# rev02_16.net
KiCad netlist of a schematic drawn in Altium Designer
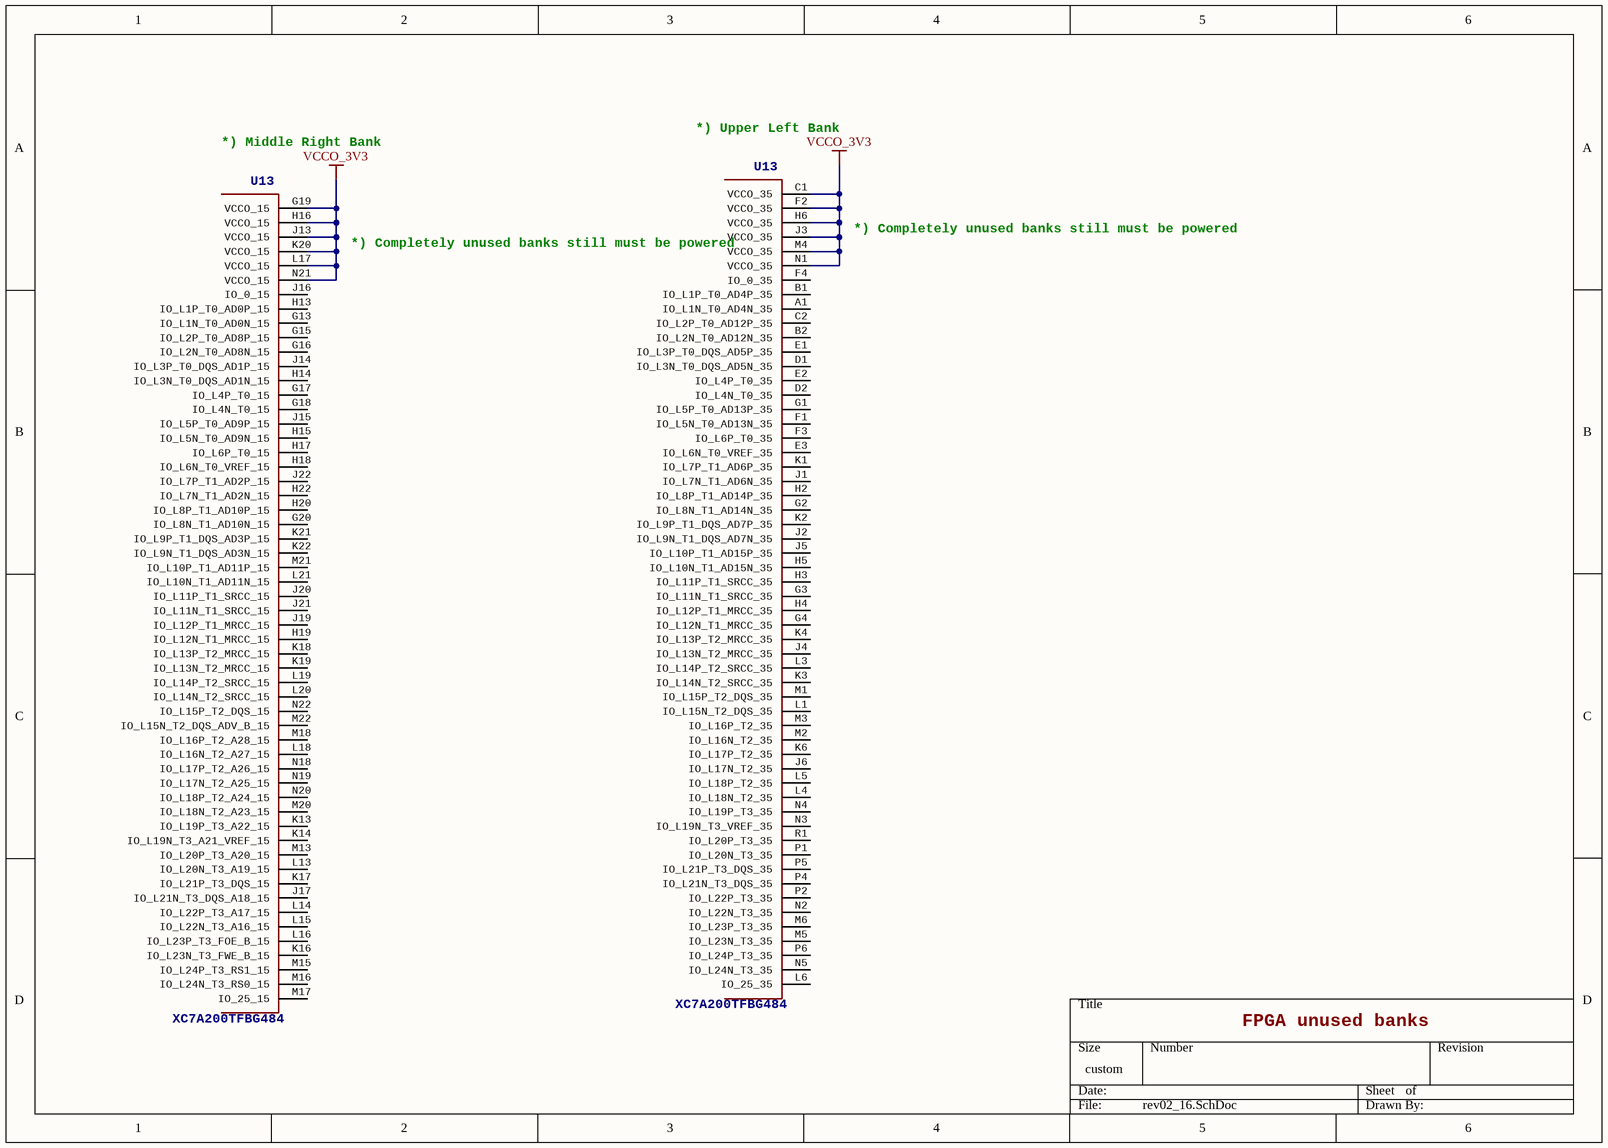
[diagram p0: rev02_16.SchDoc]

(export (version "E")
  (design (tool "Eeschema 10.0.6"))
  (components
    (comp (ref "U13")
      (value "XC7A200TFBG484")
      (footprint "BGA484C100P22X22_2300X2300X254")
      (description "Xilinx FPGA: XC7A200TFBG484")
      (fields
        (field (name "MFR") "Xilinx")
        (field (name "MPN") "XC7A200T-1FBG484C")
        (field (name ">NAME") "U13")
        (field (name ">VALUE") "XC7A200TFBG484")
      )
      (libsource (lib "Xilinx_XC7A200TFBG484") (part "XC7A200TFBG484"))
    )
  )
  (nets
    (net (code "1") (name "VCCO_3V3") (class "Default")
      (node (ref "U13") (pin "C1") (pinfunction "VCCO_35_C1") (pintype "passive"))
      (node (ref "U13") (pin "F2") (pinfunction "VCCO_35_F2") (pintype "passive"))
      (node (ref "U13") (pin "G19") (pinfunction "VCCO_15_G19") (pintype "passive"))
      (node (ref "U13") (pin "H16") (pinfunction "VCCO_15_H16") (pintype "passive"))
      (node (ref "U13") (pin "H6") (pinfunction "VCCO_35_H6") (pintype "passive"))
      (node (ref "U13") (pin "J13") (pinfunction "VCCO_15_J13") (pintype "passive"))
      (node (ref "U13") (pin "J3") (pinfunction "VCCO_35_J3") (pintype "passive"))
      (node (ref "U13") (pin "K20") (pinfunction "VCCO_15_K20") (pintype "passive"))
      (node (ref "U13") (pin "L17") (pinfunction "VCCO_15_L17") (pintype "passive"))
      (node (ref "U13") (pin "M4") (pinfunction "VCCO_35_M4") (pintype "passive"))
      (node (ref "U13") (pin "N1") (pinfunction "VCCO_35_N1") (pintype "passive"))
      (node (ref "U13") (pin "N21") (pinfunction "VCCO_15_N21") (pintype "passive"))
    )
    (net (code "2") (name "unconnected-(U13D-IO_0_15-PadJ16)") (class "Default")
      (node (ref "U13") (pin "J16") (pinfunction "IO_0_15_J16") (pintype "passive"))
    )
    (net (code "3") (name "unconnected-(U13D-IO_25_15-PadM17)") (class "Default")
      (node (ref "U13") (pin "M17") (pinfunction "IO_25_15_M17") (pintype "passive"))
    )
    (net (code "4") (name "unconnected-(U13D-IO_L1N_T0_AD0N_15-PadG13)") (class "Default")
      (node (ref "U13") (pin "G13") (pinfunction "IO_L1N_T0_AD0N_15_G13") (pintype "passive"))
    )
    (net (code "5") (name "unconnected-(U13D-IO_L1P_T0_AD0P_15-PadH13)") (class "Default")
      (node (ref "U13") (pin "H13") (pinfunction "IO_L1P_T0_AD0P_15_H13") (pintype "passive"))
    )
    (net (code "6") (name "unconnected-(U13D-IO_L2N_T0_AD8N_15-PadG16)") (class "Default")
      (node (ref "U13") (pin "G16") (pinfunction "IO_L2N_T0_AD8N_15_G16") (pintype "passive"))
    )
    (net (code "7") (name "unconnected-(U13D-IO_L2P_T0_AD8P_15-PadG15)") (class "Default")
      (node (ref "U13") (pin "G15") (pinfunction "IO_L2P_T0_AD8P_15_G15") (pintype "passive"))
    )
    (net (code "8") (name "unconnected-(U13D-IO_L3N_T0_DQS_AD1N_15-PadH14)") (class "Default")
      (node (ref "U13") (pin "H14") (pinfunction "IO_L3N_T0_DQS_AD1N_15_H14") (pintype "passive"))
    )
    (net (code "9") (name "unconnected-(U13D-IO_L3P_T0_DQS_AD1P_15-PadJ14)") (class "Default")
      (node (ref "U13") (pin "J14") (pinfunction "IO_L3P_T0_DQS_AD1P_15_J14") (pintype "passive"))
    )
    (net (code "10") (name "unconnected-(U13D-IO_L4N_T0_15-PadG18)") (class "Default")
      (node (ref "U13") (pin "G18") (pinfunction "IO_L4N_T0_15_G18") (pintype "passive"))
    )
    (net (code "11") (name "unconnected-(U13D-IO_L4P_T0_15-PadG17)") (class "Default")
      (node (ref "U13") (pin "G17") (pinfunction "IO_L4P_T0_15_G17") (pintype "passive"))
    )
    (net (code "12") (name "unconnected-(U13D-IO_L5N_T0_AD9N_15-PadH15)") (class "Default")
      (node (ref "U13") (pin "H15") (pinfunction "IO_L5N_T0_AD9N_15_H15") (pintype "passive"))
    )
    (net (code "13") (name "unconnected-(U13D-IO_L5P_T0_AD9P_15-PadJ15)") (class "Default")
      (node (ref "U13") (pin "J15") (pinfunction "IO_L5P_T0_AD9P_15_J15") (pintype "passive"))
    )
    (net (code "14") (name "unconnected-(U13D-IO_L6N_T0_VREF_15-PadH18)") (class "Default")
      (node (ref "U13") (pin "H18") (pinfunction "IO_L6N_T0_VREF_15_H18") (pintype "passive"))
    )
    (net (code "15") (name "unconnected-(U13D-IO_L6P_T0_15-PadH17)") (class "Default")
      (node (ref "U13") (pin "H17") (pinfunction "IO_L6P_T0_15_H17") (pintype "passive"))
    )
    (net (code "16") (name "unconnected-(U13D-IO_L7N_T1_AD2N_15-PadH22)") (class "Default")
      (node (ref "U13") (pin "H22") (pinfunction "IO_L7N_T1_AD2N_15_H22") (pintype "passive"))
    )
    (net (code "17") (name "unconnected-(U13D-IO_L7P_T1_AD2P_15-PadJ22)") (class "Default")
      (node (ref "U13") (pin "J22") (pinfunction "IO_L7P_T1_AD2P_15_J22") (pintype "passive"))
    )
    (net (code "18") (name "unconnected-(U13D-IO_L8N_T1_AD10N_15-PadG20)") (class "Default")
      (node (ref "U13") (pin "G20") (pinfunction "IO_L8N_T1_AD10N_15_G20") (pintype "passive"))
    )
    (net (code "19") (name "unconnected-(U13D-IO_L8P_T1_AD10P_15-PadH20)") (class "Default")
      (node (ref "U13") (pin "H20") (pinfunction "IO_L8P_T1_AD10P_15_H20") (pintype "passive"))
    )
    (net (code "20") (name "unconnected-(U13D-IO_L9N_T1_DQS_AD3N_15-PadK22)") (class "Default")
      (node (ref "U13") (pin "K22") (pinfunction "IO_L9N_T1_DQS_AD3N_15_K22") (pintype "passive"))
    )
    (net (code "21") (name "unconnected-(U13D-IO_L9P_T1_DQS_AD3P_15-PadK21)") (class "Default")
      (node (ref "U13") (pin "K21") (pinfunction "IO_L9P_T1_DQS_AD3P_15_K21") (pintype "passive"))
    )
    (net (code "22") (name "unconnected-(U13D-IO_L10N_T1_AD11N_15-PadL21)") (class "Default")
      (node (ref "U13") (pin "L21") (pinfunction "IO_L10N_T1_AD11N_15_L21") (pintype "passive"))
    )
    (net (code "23") (name "unconnected-(U13D-IO_L10P_T1_AD11P_15-PadM21)") (class "Default")
      (node (ref "U13") (pin "M21") (pinfunction "IO_L10P_T1_AD11P_15_M21") (pintype "passive"))
    )
    (net (code "24") (name "unconnected-(U13D-IO_L11N_T1_SRCC_15-PadJ21)") (class "Default")
      (node (ref "U13") (pin "J21") (pinfunction "IO_L11N_T1_SRCC_15_J21") (pintype "passive"))
    )
    (net (code "25") (name "unconnected-(U13D-IO_L11P_T1_SRCC_15-PadJ20)") (class "Default")
      (node (ref "U13") (pin "J20") (pinfunction "IO_L11P_T1_SRCC_15_J20") (pintype "passive"))
    )
    (net (code "26") (name "unconnected-(U13D-IO_L12N_T1_MRCC_15-PadH19)") (class "Default")
      (node (ref "U13") (pin "H19") (pinfunction "IO_L12N_T1_MRCC_15_H19") (pintype "passive"))
    )
    (net (code "27") (name "unconnected-(U13D-IO_L12P_T1_MRCC_15-PadJ19)") (class "Default")
      (node (ref "U13") (pin "J19") (pinfunction "IO_L12P_T1_MRCC_15_J19") (pintype "passive"))
    )
    (net (code "28") (name "unconnected-(U13D-IO_L13N_T2_MRCC_15-PadK19)") (class "Default")
      (node (ref "U13") (pin "K19") (pinfunction "IO_L13N_T2_MRCC_15_K19") (pintype "passive"))
    )
    (net (code "29") (name "unconnected-(U13D-IO_L13P_T2_MRCC_15-PadK18)") (class "Default")
      (node (ref "U13") (pin "K18") (pinfunction "IO_L13P_T2_MRCC_15_K18") (pintype "passive"))
    )
    (net (code "30") (name "unconnected-(U13D-IO_L14N_T2_SRCC_15-PadL20)") (class "Default")
      (node (ref "U13") (pin "L20") (pinfunction "IO_L14N_T2_SRCC_15_L20") (pintype "passive"))
    )
    (net (code "31") (name "unconnected-(U13D-IO_L14P_T2_SRCC_15-PadL19)") (class "Default")
      (node (ref "U13") (pin "L19") (pinfunction "IO_L14P_T2_SRCC_15_L19") (pintype "passive"))
    )
    (net (code "32") (name "unconnected-(U13D-IO_L15N_T2_DQS_ADV_B_15-PadM22)") (class "Default")
      (node (ref "U13") (pin "M22") (pinfunction "IO_L15N_T2_DQS_ADV_B_15_M22") (pintype "passive"))
    )
    (net (code "33") (name "unconnected-(U13D-IO_L15P_T2_DQS_15-PadN22)") (class "Default")
      (node (ref "U13") (pin "N22") (pinfunction "IO_L15P_T2_DQS_15_N22") (pintype "passive"))
    )
    (net (code "34") (name "unconnected-(U13D-IO_L16N_T2_A27_15-PadL18)") (class "Default")
      (node (ref "U13") (pin "L18") (pinfunction "IO_L16N_T2_A27_15_L18") (pintype "passive"))
    )
    (net (code "35") (name "unconnected-(U13D-IO_L16P_T2_A28_15-PadM18)") (class "Default")
      (node (ref "U13") (pin "M18") (pinfunction "IO_L16P_T2_A28_15_M18") (pintype "passive"))
    )
    (net (code "36") (name "unconnected-(U13D-IO_L17N_T2_A25_15-PadN19)") (class "Default")
      (node (ref "U13") (pin "N19") (pinfunction "IO_L17N_T2_A25_15_N19") (pintype "passive"))
    )
    (net (code "37") (name "unconnected-(U13D-IO_L17P_T2_A26_15-PadN18)") (class "Default")
      (node (ref "U13") (pin "N18") (pinfunction "IO_L17P_T2_A26_15_N18") (pintype "passive"))
    )
    (net (code "38") (name "unconnected-(U13D-IO_L18N_T2_A23_15-PadM20)") (class "Default")
      (node (ref "U13") (pin "M20") (pinfunction "IO_L18N_T2_A23_15_M20") (pintype "passive"))
    )
    (net (code "39") (name "unconnected-(U13D-IO_L18P_T2_A24_15-PadN20)") (class "Default")
      (node (ref "U13") (pin "N20") (pinfunction "IO_L18P_T2_A24_15_N20") (pintype "passive"))
    )
    (net (code "40") (name "unconnected-(U13D-IO_L19N_T3_A21_VREF_15-PadK14)") (class "Default")
      (node (ref "U13") (pin "K14") (pinfunction "IO_L19N_T3_A21_VREF_15_K14") (pintype "passive"))
    )
    (net (code "41") (name "unconnected-(U13D-IO_L19P_T3_A22_15-PadK13)") (class "Default")
      (node (ref "U13") (pin "K13") (pinfunction "IO_L19P_T3_A22_15_K13") (pintype "passive"))
    )
    (net (code "42") (name "unconnected-(U13D-IO_L20N_T3_A19_15-PadL13)") (class "Default")
      (node (ref "U13") (pin "L13") (pinfunction "IO_L20N_T3_A19_15_L13") (pintype "passive"))
    )
    (net (code "43") (name "unconnected-(U13D-IO_L20P_T3_A20_15-PadM13)") (class "Default")
      (node (ref "U13") (pin "M13") (pinfunction "IO_L20P_T3_A20_15_M13") (pintype "passive"))
    )
    (net (code "44") (name "unconnected-(U13D-IO_L21N_T3_DQS_A18_15-PadJ17)") (class "Default")
      (node (ref "U13") (pin "J17") (pinfunction "IO_L21N_T3_DQS_A18_15_J17") (pintype "passive"))
    )
    (net (code "45") (name "unconnected-(U13D-IO_L21P_T3_DQS_15-PadK17)") (class "Default")
      (node (ref "U13") (pin "K17") (pinfunction "IO_L21P_T3_DQS_15_K17") (pintype "passive"))
    )
    (net (code "46") (name "unconnected-(U13D-IO_L22N_T3_A16_15-PadL15)") (class "Default")
      (node (ref "U13") (pin "L15") (pinfunction "IO_L22N_T3_A16_15_L15") (pintype "passive"))
    )
    (net (code "47") (name "unconnected-(U13D-IO_L22P_T3_A17_15-PadL14)") (class "Default")
      (node (ref "U13") (pin "L14") (pinfunction "IO_L22P_T3_A17_15_L14") (pintype "passive"))
    )
    (net (code "48") (name "unconnected-(U13D-IO_L23N_T3_FWE_B_15-PadK16)") (class "Default")
      (node (ref "U13") (pin "K16") (pinfunction "IO_L23N_T3_FWE_B_15_K16") (pintype "passive"))
    )
    (net (code "49") (name "unconnected-(U13D-IO_L23P_T3_FOE_B_15-PadL16)") (class "Default")
      (node (ref "U13") (pin "L16") (pinfunction "IO_L23P_T3_FOE_B_15_L16") (pintype "passive"))
    )
    (net (code "50") (name "unconnected-(U13D-IO_L24N_T3_RS0_15-PadM16)") (class "Default")
      (node (ref "U13") (pin "M16") (pinfunction "IO_L24N_T3_RS0_15_M16") (pintype "passive"))
    )
    (net (code "51") (name "unconnected-(U13D-IO_L24P_T3_RS1_15-PadM15)") (class "Default")
      (node (ref "U13") (pin "M15") (pinfunction "IO_L24P_T3_RS1_15_M15") (pintype "passive"))
    )
    (net (code "52") (name "unconnected-(U13G-IO_0_35-PadF4)") (class "Default")
      (node (ref "U13") (pin "F4") (pinfunction "IO_0_35_F4") (pintype "passive"))
    )
    (net (code "53") (name "unconnected-(U13G-IO_25_35-PadL6)") (class "Default")
      (node (ref "U13") (pin "L6") (pinfunction "IO_25_35_L6") (pintype "passive"))
    )
    (net (code "54") (name "unconnected-(U13G-IO_L1N_T0_AD4N_35-PadA1)") (class "Default")
      (node (ref "U13") (pin "A1") (pinfunction "IO_L1N_T0_AD4N_35_A1") (pintype "passive"))
    )
    (net (code "55") (name "unconnected-(U13G-IO_L1P_T0_AD4P_35-PadB1)") (class "Default")
      (node (ref "U13") (pin "B1") (pinfunction "IO_L1P_T0_AD4P_35_B1") (pintype "passive"))
    )
    (net (code "56") (name "unconnected-(U13G-IO_L2N_T0_AD12N_35-PadB2)") (class "Default")
      (node (ref "U13") (pin "B2") (pinfunction "IO_L2N_T0_AD12N_35_B2") (pintype "passive"))
    )
    (net (code "57") (name "unconnected-(U13G-IO_L2P_T0_AD12P_35-PadC2)") (class "Default")
      (node (ref "U13") (pin "C2") (pinfunction "IO_L2P_T0_AD12P_35_C2") (pintype "passive"))
    )
    (net (code "58") (name "unconnected-(U13G-IO_L3N_T0_DQS_AD5N_35-PadD1)") (class "Default")
      (node (ref "U13") (pin "D1") (pinfunction "IO_L3N_T0_DQS_AD5N_35_D1") (pintype "passive"))
    )
    (net (code "59") (name "unconnected-(U13G-IO_L3P_T0_DQS_AD5P_35-PadE1)") (class "Default")
      (node (ref "U13") (pin "E1") (pinfunction "IO_L3P_T0_DQS_AD5P_35_E1") (pintype "passive"))
    )
    (net (code "60") (name "unconnected-(U13G-IO_L4N_T0_35-PadD2)") (class "Default")
      (node (ref "U13") (pin "D2") (pinfunction "IO_L4N_T0_35_D2") (pintype "passive"))
    )
    (net (code "61") (name "unconnected-(U13G-IO_L4P_T0_35-PadE2)") (class "Default")
      (node (ref "U13") (pin "E2") (pinfunction "IO_L4P_T0_35_E2") (pintype "passive"))
    )
    (net (code "62") (name "unconnected-(U13G-IO_L5N_T0_AD13N_35-PadF1)") (class "Default")
      (node (ref "U13") (pin "F1") (pinfunction "IO_L5N_T0_AD13N_35_F1") (pintype "passive"))
    )
    (net (code "63") (name "unconnected-(U13G-IO_L5P_T0_AD13P_35-PadG1)") (class "Default")
      (node (ref "U13") (pin "G1") (pinfunction "IO_L5P_T0_AD13P_35_G1") (pintype "passive"))
    )
    (net (code "64") (name "unconnected-(U13G-IO_L6N_T0_VREF_35-PadE3)") (class "Default")
      (node (ref "U13") (pin "E3") (pinfunction "IO_L6N_T0_VREF_35_E3") (pintype "passive"))
    )
    (net (code "65") (name "unconnected-(U13G-IO_L6P_T0_35-PadF3)") (class "Default")
      (node (ref "U13") (pin "F3") (pinfunction "IO_L6P_T0_35_F3") (pintype "passive"))
    )
    (net (code "66") (name "unconnected-(U13G-IO_L7N_T1_AD6N_35-PadJ1)") (class "Default")
      (node (ref "U13") (pin "J1") (pinfunction "IO_L7N_T1_AD6N_35_J1") (pintype "passive"))
    )
    (net (code "67") (name "unconnected-(U13G-IO_L7P_T1_AD6P_35-PadK1)") (class "Default")
      (node (ref "U13") (pin "K1") (pinfunction "IO_L7P_T1_AD6P_35_K1") (pintype "passive"))
    )
    (net (code "68") (name "unconnected-(U13G-IO_L8N_T1_AD14N_35-PadG2)") (class "Default")
      (node (ref "U13") (pin "G2") (pinfunction "IO_L8N_T1_AD14N_35_G2") (pintype "passive"))
    )
    (net (code "69") (name "unconnected-(U13G-IO_L8P_T1_AD14P_35-PadH2)") (class "Default")
      (node (ref "U13") (pin "H2") (pinfunction "IO_L8P_T1_AD14P_35_H2") (pintype "passive"))
    )
    (net (code "70") (name "unconnected-(U13G-IO_L9N_T1_DQS_AD7N_35-PadJ2)") (class "Default")
      (node (ref "U13") (pin "J2") (pinfunction "IO_L9N_T1_DQS_AD7N_35_J2") (pintype "passive"))
    )
    (net (code "71") (name "unconnected-(U13G-IO_L9P_T1_DQS_AD7P_35-PadK2)") (class "Default")
      (node (ref "U13") (pin "K2") (pinfunction "IO_L9P_T1_DQS_AD7P_35_K2") (pintype "passive"))
    )
    (net (code "72") (name "unconnected-(U13G-IO_L10N_T1_AD15N_35-PadH5)") (class "Default")
      (node (ref "U13") (pin "H5") (pinfunction "IO_L10N_T1_AD15N_35_H5") (pintype "passive"))
    )
    (net (code "73") (name "unconnected-(U13G-IO_L10P_T1_AD15P_35-PadJ5)") (class "Default")
      (node (ref "U13") (pin "J5") (pinfunction "IO_L10P_T1_AD15P_35_J5") (pintype "passive"))
    )
    (net (code "74") (name "unconnected-(U13G-IO_L11N_T1_SRCC_35-PadG3)") (class "Default")
      (node (ref "U13") (pin "G3") (pinfunction "IO_L11N_T1_SRCC_35_G3") (pintype "passive"))
    )
    (net (code "75") (name "unconnected-(U13G-IO_L11P_T1_SRCC_35-PadH3)") (class "Default")
      (node (ref "U13") (pin "H3") (pinfunction "IO_L11P_T1_SRCC_35_H3") (pintype "passive"))
    )
    (net (code "76") (name "unconnected-(U13G-IO_L12N_T1_MRCC_35-PadG4)") (class "Default")
      (node (ref "U13") (pin "G4") (pinfunction "IO_L12N_T1_MRCC_35_G4") (pintype "passive"))
    )
    (net (code "77") (name "unconnected-(U13G-IO_L12P_T1_MRCC_35-PadH4)") (class "Default")
      (node (ref "U13") (pin "H4") (pinfunction "IO_L12P_T1_MRCC_35_H4") (pintype "passive"))
    )
    (net (code "78") (name "unconnected-(U13G-IO_L13N_T2_MRCC_35-PadJ4)") (class "Default")
      (node (ref "U13") (pin "J4") (pinfunction "IO_L13N_T2_MRCC_35_J4") (pintype "passive"))
    )
    (net (code "79") (name "unconnected-(U13G-IO_L13P_T2_MRCC_35-PadK4)") (class "Default")
      (node (ref "U13") (pin "K4") (pinfunction "IO_L13P_T2_MRCC_35_K4") (pintype "passive"))
    )
    (net (code "80") (name "unconnected-(U13G-IO_L14N_T2_SRCC_35-PadK3)") (class "Default")
      (node (ref "U13") (pin "K3") (pinfunction "IO_L14N_T2_SRCC_35_K3") (pintype "passive"))
    )
    (net (code "81") (name "unconnected-(U13G-IO_L14P_T2_SRCC_35-PadL3)") (class "Default")
      (node (ref "U13") (pin "L3") (pinfunction "IO_L14P_T2_SRCC_35_L3") (pintype "passive"))
    )
    (net (code "82") (name "unconnected-(U13G-IO_L15N_T2_DQS_35-PadL1)") (class "Default")
      (node (ref "U13") (pin "L1") (pinfunction "IO_L15N_T2_DQS_35_L1") (pintype "passive"))
    )
    (net (code "83") (name "unconnected-(U13G-IO_L15P_T2_DQS_35-PadM1)") (class "Default")
      (node (ref "U13") (pin "M1") (pinfunction "IO_L15P_T2_DQS_35_M1") (pintype "passive"))
    )
    (net (code "84") (name "unconnected-(U13G-IO_L16N_T2_35-PadM2)") (class "Default")
      (node (ref "U13") (pin "M2") (pinfunction "IO_L16N_T2_35_M2") (pintype "passive"))
    )
    (net (code "85") (name "unconnected-(U13G-IO_L16P_T2_35-PadM3)") (class "Default")
      (node (ref "U13") (pin "M3") (pinfunction "IO_L16P_T2_35_M3") (pintype "passive"))
    )
    (net (code "86") (name "unconnected-(U13G-IO_L17N_T2_35-PadJ6)") (class "Default")
      (node (ref "U13") (pin "J6") (pinfunction "IO_L17N_T2_35_J6") (pintype "passive"))
    )
    (net (code "87") (name "unconnected-(U13G-IO_L17P_T2_35-PadK6)") (class "Default")
      (node (ref "U13") (pin "K6") (pinfunction "IO_L17P_T2_35_K6") (pintype "passive"))
    )
    (net (code "88") (name "unconnected-(U13G-IO_L18N_T2_35-PadL4)") (class "Default")
      (node (ref "U13") (pin "L4") (pinfunction "IO_L18N_T2_35_L4") (pintype "passive"))
    )
    (net (code "89") (name "unconnected-(U13G-IO_L18P_T2_35-PadL5)") (class "Default")
      (node (ref "U13") (pin "L5") (pinfunction "IO_L18P_T2_35_L5") (pintype "passive"))
    )
    (net (code "90") (name "unconnected-(U13G-IO_L19N_T3_VREF_35-PadN3)") (class "Default")
      (node (ref "U13") (pin "N3") (pinfunction "IO_L19N_T3_VREF_35_N3") (pintype "passive"))
    )
    (net (code "91") (name "unconnected-(U13G-IO_L19P_T3_35-PadN4)") (class "Default")
      (node (ref "U13") (pin "N4") (pinfunction "IO_L19P_T3_35_N4") (pintype "passive"))
    )
    (net (code "92") (name "unconnected-(U13G-IO_L20N_T3_35-PadP1)") (class "Default")
      (node (ref "U13") (pin "P1") (pinfunction "IO_L20N_T3_35_P1") (pintype "passive"))
    )
    (net (code "93") (name "unconnected-(U13G-IO_L20P_T3_35-PadR1)") (class "Default")
      (node (ref "U13") (pin "R1") (pinfunction "IO_L20P_T3_35_R1") (pintype "passive"))
    )
    (net (code "94") (name "unconnected-(U13G-IO_L21N_T3_DQS_35-PadP4)") (class "Default")
      (node (ref "U13") (pin "P4") (pinfunction "IO_L21N_T3_DQS_35_P4") (pintype "passive"))
    )
    (net (code "95") (name "unconnected-(U13G-IO_L21P_T3_DQS_35-PadP5)") (class "Default")
      (node (ref "U13") (pin "P5") (pinfunction "IO_L21P_T3_DQS_35_P5") (pintype "passive"))
    )
    (net (code "96") (name "unconnected-(U13G-IO_L22N_T3_35-PadN2)") (class "Default")
      (node (ref "U13") (pin "N2") (pinfunction "IO_L22N_T3_35_N2") (pintype "passive"))
    )
    (net (code "97") (name "unconnected-(U13G-IO_L22P_T3_35-PadP2)") (class "Default")
      (node (ref "U13") (pin "P2") (pinfunction "IO_L22P_T3_35_P2") (pintype "passive"))
    )
    (net (code "98") (name "unconnected-(U13G-IO_L23N_T3_35-PadM5)") (class "Default")
      (node (ref "U13") (pin "M5") (pinfunction "IO_L23N_T3_35_M5") (pintype "passive"))
    )
    (net (code "99") (name "unconnected-(U13G-IO_L23P_T3_35-PadM6)") (class "Default")
      (node (ref "U13") (pin "M6") (pinfunction "IO_L23P_T3_35_M6") (pintype "passive"))
    )
    (net (code "100") (name "unconnected-(U13G-IO_L24N_T3_35-PadN5)") (class "Default")
      (node (ref "U13") (pin "N5") (pinfunction "IO_L24N_T3_35_N5") (pintype "passive"))
    )
    (net (code "101") (name "unconnected-(U13G-IO_L24P_T3_35-PadP6)") (class "Default")
      (node (ref "U13") (pin "P6") (pinfunction "IO_L24P_T3_35_P6") (pintype "passive"))
    )
  )
)
